# Qwiic_PT100.net
KiCad netlist of a schematic drawn in EAGLE
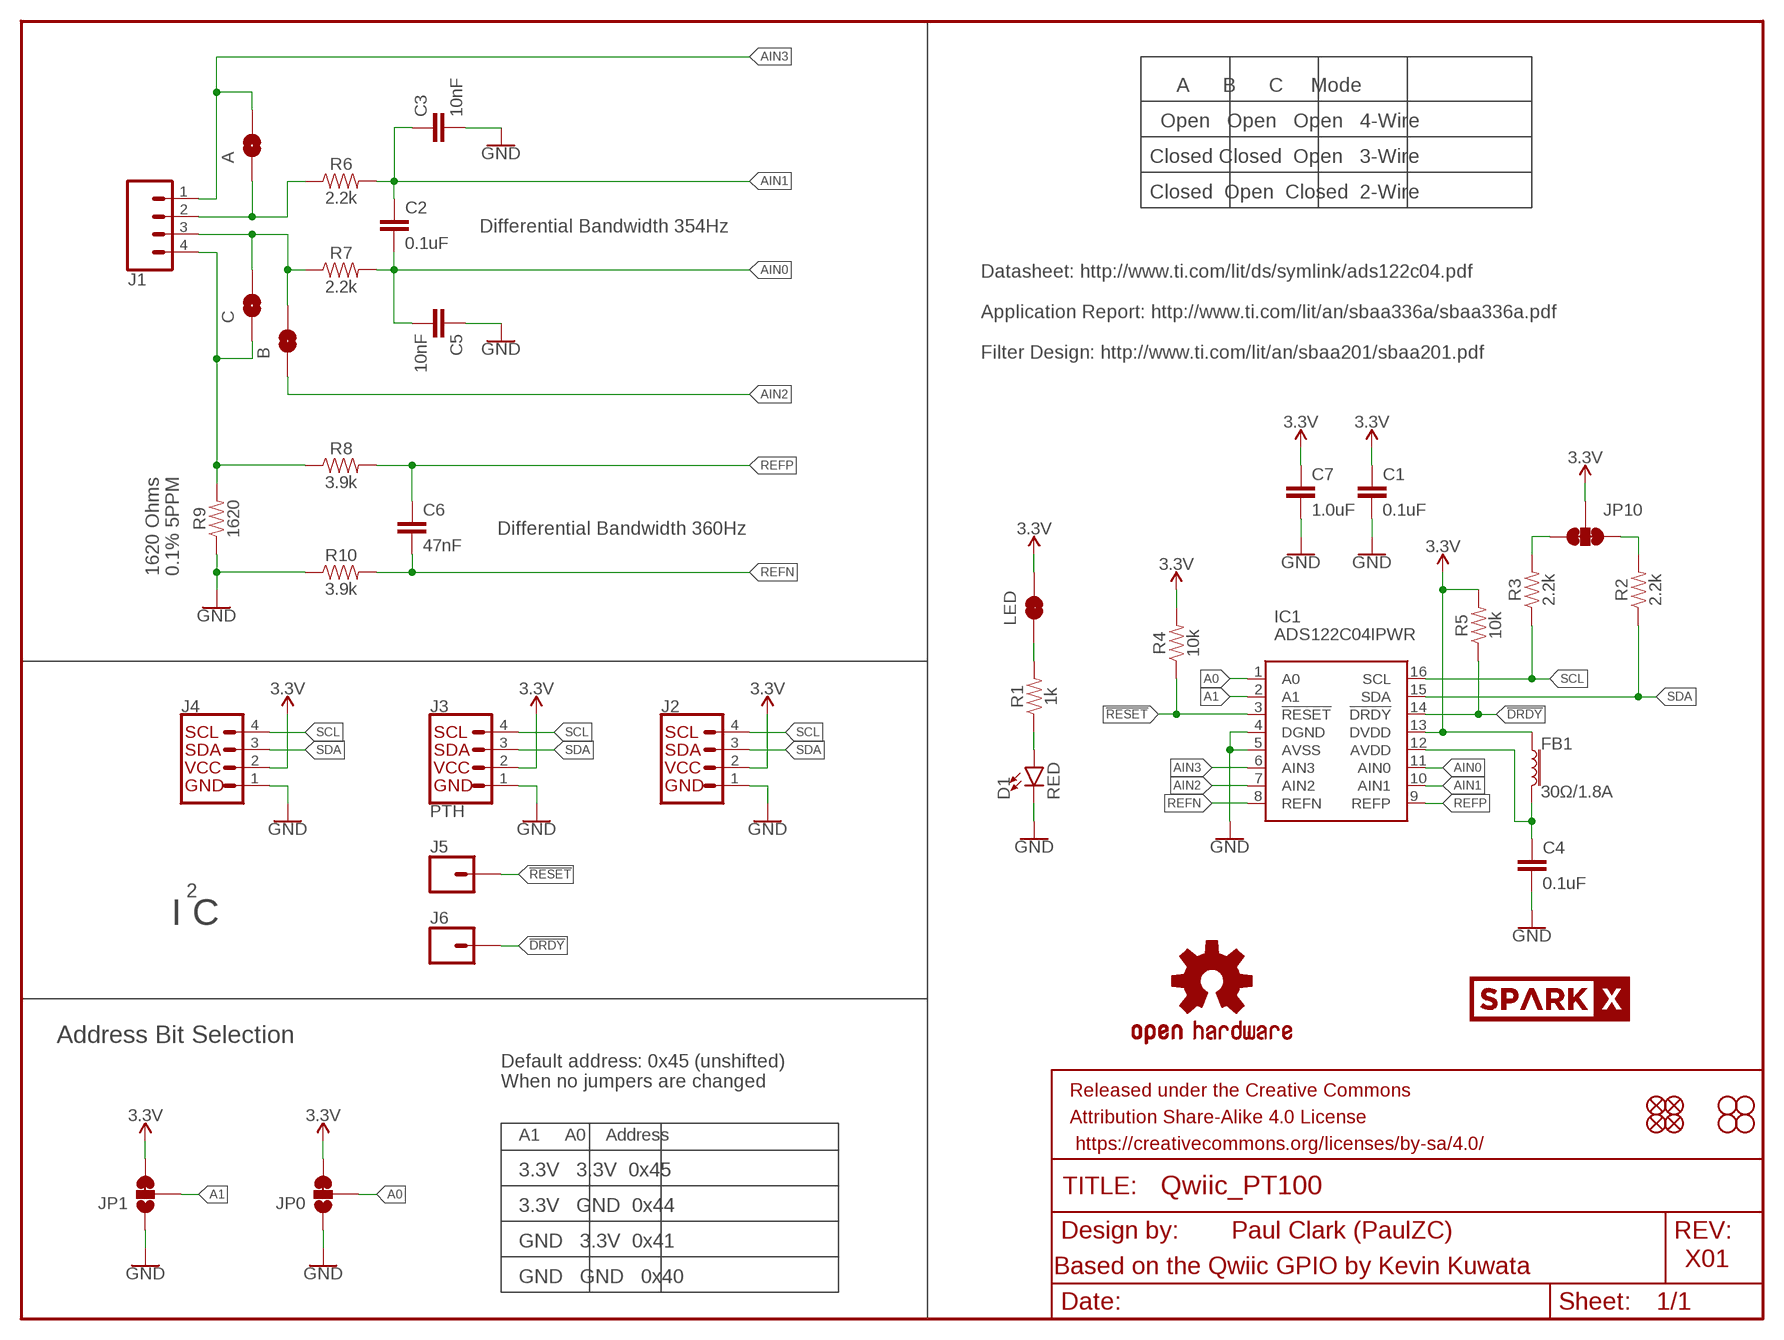
[diagram p0: schematic, sheet 1]

(export (version "E")
  (design (tool "Eeschema 10.0.6"))
  (components
    (comp (ref "A")
      (value "JUMPER-SMT_2_NO_SILK_ROUND")
      (footprint "eagle-import:SMT-JUMPER_2_NO_SILK_ROUND")
      (libsource (lib "eagle-import") (part "JUMPER-SMT_2_NO_SILK_ROUND"))
    )
    (comp (ref "B")
      (value "JUMPER-SMT_2_NO_SILK_ROUND")
      (footprint "eagle-import:SMT-JUMPER_2_NO_SILK_ROUND")
      (libsource (lib "eagle-import") (part "JUMPER-SMT_2_NO_SILK_ROUND"))
    )
    (comp (ref "C")
      (value "JUMPER-SMT_2_NO_SILK_ROUND")
      (footprint "eagle-import:SMT-JUMPER_2_NO_SILK_ROUND")
      (libsource (lib "eagle-import") (part "JUMPER-SMT_2_NO_SILK_ROUND"))
    )
    (comp (ref "C1")
      (value "0.1uF")
      (footprint "eagle-import:0603")
      (libsource (lib "eagle-import") (part "0.1UF-0603-25V-(+80/-20%)"))
    )
    (comp (ref "C2")
      (value "0.1uF")
      (footprint "eagle-import:0603")
      (libsource (lib "eagle-import") (part "0.1UF-0603-25V-5%"))
    )
    (comp (ref "C3")
      (value "10nF")
      (footprint "eagle-import:0603")
      (libsource (lib "eagle-import") (part "10NF-0603-50V-10%"))
    )
    (comp (ref "C4")
      (value "0.1uF")
      (footprint "eagle-import:0603")
      (libsource (lib "eagle-import") (part "0.1UF-0603-25V-(+80/-20%)"))
    )
    (comp (ref "C5")
      (value "10nF")
      (footprint "eagle-import:0603")
      (libsource (lib "eagle-import") (part "10NF-0603-50V-10%"))
    )
    (comp (ref "C6")
      (value "47nF")
      (footprint "eagle-import:0603")
      (libsource (lib "eagle-import") (part "47NF-0603-25V-5%"))
    )
    (comp (ref "C7")
      (value "1.0uF")
      (footprint "eagle-import:0603")
      (libsource (lib "eagle-import") (part "1.0UF-0603-16V-10%-X7R"))
    )
    (comp (ref "D1")
      (value "RED")
      (footprint "eagle-import:LED-0603")
      (libsource (lib "eagle-import") (part "LED-RED0603"))
    )
    (comp (ref "FB1")
      (value "30Ω/1.8A")
      (footprint "eagle-import:0603")
      (libsource (lib "eagle-import") (part "FERRITE_BEAD-0603"))
    )
    (comp (ref "FD1")
      (value "FIDUCIAL1X2")
      (footprint "eagle-import:FIDUCIAL-1X2")
      (libsource (lib "eagle-import") (part "FIDUCIAL1X2"))
    )
    (comp (ref "FD2")
      (value "FIDUCIAL1X2")
      (footprint "eagle-import:FIDUCIAL-1X2")
      (libsource (lib "eagle-import") (part "FIDUCIAL1X2"))
    )
    (comp (ref "FRAME1")
      (value "FRAME-LETTER")
      (footprint "eagle-import:CREATIVE_COMMONS")
      (libsource (lib "eagle-import") (part "FRAME-LETTER"))
    )
    (comp (ref "H1")
      (value "STAND-OFF")
      (footprint "eagle-import:STAND-OFF")
      (libsource (lib "eagle-import") (part "STAND-OFF"))
    )
    (comp (ref "H2")
      (value "STAND-OFF")
      (footprint "eagle-import:STAND-OFF")
      (libsource (lib "eagle-import") (part "STAND-OFF"))
    )
    (comp (ref "IC1")
      (value "ADS122C04IPWR")
      (footprint "eagle-import:SOP65P640X120-16N")
      (fields (field (name "MOUSER_PART_NUMBER") "595-ADS122C04IPWR"))
      (libsource (lib "eagle-import") (part "ADS122C04IPWR"))
    )
    (comp (ref "J1")
      (value "CONN_04LATCH")
      (footprint "eagle-import:LATCHTERMINAL-5MM-4")
      (fields (field (name "PROD_ID") "CON-14722"))
      (libsource (lib "eagle-import") (part "CONN_04LATCH"))
    )
    (comp (ref "J2")
      (value "QWIIC_RIGHT_ANGLE")
      (footprint "eagle-import:JST04_1MM_RA")
      (fields (field (name "PROD_ID") "CONN-13694"))
      (libsource (lib "eagle-import") (part "QWIIC_CONNECTORJS-1MM"))
    )
    (comp (ref "J3")
      (value "PTH")
      (footprint "eagle-import:1X04_NO_SILK")
      (libsource (lib "eagle-import") (part "I2C_STANDARD_NO_SILK"))
    )
    (comp (ref "J4")
      (value "QWIIC_RIGHT_ANGLE")
      (footprint "eagle-import:JST04_1MM_RA")
      (fields (field (name "PROD_ID") "CONN-13694"))
      (libsource (lib "eagle-import") (part "QWIIC_CONNECTORJS-1MM"))
    )
    (comp (ref "J5")
      (value "CONN_01PTH_NO_SILK_YES_STOP")
      (footprint "eagle-import:1X01_NO_SILK")
      (libsource (lib "eagle-import") (part "CONN_01PTH_NO_SILK_YES_STOP"))
    )
    (comp (ref "J6")
      (value "CONN_01PTH_NO_SILK_YES_STOP")
      (footprint "eagle-import:1X01_NO_SILK")
      (libsource (lib "eagle-import") (part "CONN_01PTH_NO_SILK_YES_STOP"))
    )
    (comp (ref "JP0")
      (value "JUMPER-SMT_3_1-NC_TRACE_SILK")
      (footprint "eagle-import:SMT-JUMPER_3_1-NC_TRACE_SILK")
      (libsource (lib "eagle-import") (part "JUMPER-SMT_3_1-NC_TRACE_SILK"))
    )
    (comp (ref "JP1")
      (value "JUMPER-SMT_3_1-NC_TRACE_SILK")
      (footprint "eagle-import:SMT-JUMPER_3_1-NC_TRACE_SILK")
      (libsource (lib "eagle-import") (part "JUMPER-SMT_3_1-NC_TRACE_SILK"))
    )
    (comp (ref "JP2")
      (value "FIDUCIAL1X2")
      (footprint "eagle-import:FIDUCIAL-1X2")
      (libsource (lib "eagle-import") (part "FIDUCIAL1X2"))
    )
    (comp (ref "JP3")
      (value "STAND-OFF")
      (footprint "eagle-import:STAND-OFF")
      (libsource (lib "eagle-import") (part "STAND-OFF"))
    )
    (comp (ref "JP4")
      (value "STAND-OFF")
      (footprint "eagle-import:STAND-OFF")
      (libsource (lib "eagle-import") (part "STAND-OFF"))
    )
    (comp (ref "JP6")
      (value "FIDUCIAL1X2")
      (footprint "eagle-import:FIDUCIAL-1X2")
      (libsource (lib "eagle-import") (part "FIDUCIAL1X2"))
    )
    (comp (ref "JP10")
      (value "JUMPER-SMT_3_2-NC_TRACE_SILK")
      (footprint "eagle-import:SMT-JUMPER_3_2-NC_TRACE_SILK")
      (libsource (lib "eagle-import") (part "JUMPER-SMT_3_2-NC_TRACE_SILK"))
    )
    (comp (ref "LED")
      (value "JUMPER-SMT_2_NC_TRACE_SILK")
      (footprint "eagle-import:SMT-JUMPER_2_NC_TRACE_SILK")
      (libsource (lib "eagle-import") (part "JUMPER-SMT_2_NC_TRACE_SILK"))
    )
    (comp (ref "LOGO1")
      (value "OSHW-LOGOMINI")
      (footprint "eagle-import:OSHW-LOGO-MINI")
      (libsource (lib "eagle-import") (part "OSHW-LOGOMINI"))
    )
    (comp (ref "R1")
      (value "1k")
      (footprint "eagle-import:0603")
      (libsource (lib "eagle-import") (part "1KOHM-0603-1/10W-1%"))
    )
    (comp (ref "R2")
      (value "2.2k")
      (footprint "eagle-import:0603")
      (libsource (lib "eagle-import") (part "2.2KOHM-0603-1/10W-1%"))
    )
    (comp (ref "R3")
      (value "2.2k")
      (footprint "eagle-import:0603")
      (libsource (lib "eagle-import") (part "2.2KOHM-0603-1/10W-1%"))
    )
    (comp (ref "R4")
      (value "10k")
      (footprint "eagle-import:0603")
      (libsource (lib "eagle-import") (part "10KOHM-0603-1/10W-1%"))
    )
    (comp (ref "R5")
      (value "10k")
      (footprint "eagle-import:0603")
      (libsource (lib "eagle-import") (part "10KOHM-0603-1/10W-1%"))
    )
    (comp (ref "R6")
      (value "2.2k")
      (footprint "eagle-import:0603")
      (libsource (lib "eagle-import") (part "2.2KOHM-0603-1/10W-1%"))
    )
    (comp (ref "R7")
      (value "2.2k")
      (footprint "eagle-import:0603")
      (libsource (lib "eagle-import") (part "2.2KOHM-0603-1/10W-1%"))
    )
    (comp (ref "R8")
      (value "3.9k")
      (footprint "eagle-import:0603")
      (libsource (lib "eagle-import") (part "3.9KOHM-0603-1/10W-1%"))
    )
    (comp (ref "R9")
      (value "1620")
      (footprint "eagle-import:0603")
      (fields (field (name "MOUSER_PART") "660-RN731JTTD1621B05") (field (name "TOLERANCE") "0.1%"))
      (libsource (lib "eagle-import") (part "RESISTOR0603"))
    )
    (comp (ref "R10")
      (value "3.9k")
      (footprint "eagle-import:0603")
      (libsource (lib "eagle-import") (part "3.9KOHM-0603-1/10W-1%"))
    )
    (comp (ref "U$1")
      (value "SPARKX-LOGO3")
      (footprint "eagle-import:SPARKX-SMALL")
      (libsource (lib "eagle-import") (part "SPARKX-LOGO3"))
    )
    (comp (ref "U$2")
      (value "SPARKX-LOGO3")
      (footprint "eagle-import:SPARKX-SMALL")
      (libsource (lib "eagle-import") (part "SPARKX-LOGO3"))
    )
  )
  (nets
    (net (code "1") (name "/~{DRDY}") (class "Default")
      (node (ref "IC1") (pin "14") (pinfunction "~{DRDY}_14") (pintype "output"))
      (node (ref "J6") (pin "1") (pinfunction "1_1") (pintype "passive"))
      (node (ref "R5") (pin "1") (pinfunction "1_1") (pintype "passive"))
    )
    (net (code "2") (name "/~{RESET}") (class "Default")
      (node (ref "IC1") (pin "3") (pinfunction "~{RESET}_3") (pintype "input"))
      (node (ref "J5") (pin "1") (pinfunction "1_1") (pintype "passive"))
      (node (ref "R4") (pin "1") (pinfunction "1_1") (pintype "passive"))
    )
    (net (code "3") (name "3.3V") (class "Default")
      (node (ref "C1") (pin "1") (pinfunction "1_1") (pintype "passive"))
      (node (ref "C7") (pin "1") (pinfunction "1_1") (pintype "passive"))
      (node (ref "FB1") (pin "1") (pinfunction "1_1") (pintype "passive"))
      (node (ref "IC1") (pin "13") (pinfunction "DVDD_13") (pintype "power_in"))
      (node (ref "J2") (pin "2") (pinfunction "2_2") (pintype "power_in"))
      (node (ref "J3") (pin "2") (pinfunction "2_2") (pintype "power_in"))
      (node (ref "J4") (pin "2") (pinfunction "2_2") (pintype "power_in"))
      (node (ref "JP0") (pin "3") (pinfunction "3_3") (pintype "passive"))
      (node (ref "JP1") (pin "3") (pinfunction "3_3") (pintype "passive"))
      (node (ref "JP10") (pin "2") (pinfunction "2_2") (pintype "passive"))
      (node (ref "LED") (pin "2") (pinfunction "2_2") (pintype "passive"))
      (node (ref "R4") (pin "2") (pinfunction "2_2") (pintype "passive"))
      (node (ref "R5") (pin "2") (pinfunction "2_2") (pintype "passive"))
    )
    (net (code "4") (name "A0") (class "Default")
      (node (ref "IC1") (pin "1") (pinfunction "A0_1") (pintype "input"))
      (node (ref "JP0") (pin "2") (pinfunction "2_2") (pintype "passive"))
    )
    (net (code "5") (name "A1") (class "Default")
      (node (ref "IC1") (pin "2") (pinfunction "A1_2") (pintype "input"))
      (node (ref "JP1") (pin "2") (pinfunction "2_2") (pintype "passive"))
    )
    (net (code "6") (name "AIN0") (class "Default")
      (node (ref "C2") (pin "2") (pinfunction "2_2") (pintype "passive"))
      (node (ref "C5") (pin "2") (pinfunction "2_2") (pintype "passive"))
      (node (ref "IC1") (pin "11") (pinfunction "AIN0_11") (pintype "input"))
      (node (ref "R7") (pin "2") (pinfunction "2_2") (pintype "passive"))
    )
    (net (code "7") (name "AIN1") (class "Default")
      (node (ref "C2") (pin "1") (pinfunction "1_1") (pintype "passive"))
      (node (ref "C3") (pin "1") (pinfunction "1_1") (pintype "passive"))
      (node (ref "IC1") (pin "10") (pinfunction "AIN1_10") (pintype "input"))
      (node (ref "R6") (pin "2") (pinfunction "2_2") (pintype "passive"))
    )
    (net (code "8") (name "AIN2") (class "Default")
      (node (ref "B") (pin "1") (pinfunction "1_1") (pintype "passive"))
      (node (ref "IC1") (pin "7") (pinfunction "AIN2_7") (pintype "input"))
    )
    (net (code "9") (name "AIN3") (class "Default")
      (node (ref "A") (pin "2") (pinfunction "2_2") (pintype "passive"))
      (node (ref "IC1") (pin "6") (pinfunction "AIN3_6") (pintype "input"))
      (node (ref "J1") (pin "1") (pinfunction "1_1") (pintype "passive"))
    )
    (net (code "10") (name "GND") (class "Default")
      (node (ref "C1") (pin "2") (pinfunction "2_2") (pintype "passive"))
      (node (ref "C3") (pin "2") (pinfunction "2_2") (pintype "passive"))
      (node (ref "C4") (pin "2") (pinfunction "2_2") (pintype "passive"))
      (node (ref "C5") (pin "1") (pinfunction "1_1") (pintype "passive"))
      (node (ref "C7") (pin "2") (pinfunction "2_2") (pintype "passive"))
      (node (ref "D1") (pin "C") (pinfunction "C_C") (pintype "passive"))
      (node (ref "IC1") (pin "4") (pinfunction "DGND_4") (pintype "power_in"))
      (node (ref "IC1") (pin "5") (pinfunction "AVSS_5") (pintype "power_in"))
      (node (ref "J2") (pin "1") (pinfunction "1_1") (pintype "power_in"))
      (node (ref "J3") (pin "1") (pinfunction "1_1") (pintype "power_in"))
      (node (ref "J4") (pin "1") (pinfunction "1_1") (pintype "power_in"))
      (node (ref "JP0") (pin "1") (pinfunction "1_1") (pintype "passive"))
      (node (ref "JP1") (pin "1") (pinfunction "1_1") (pintype "passive"))
      (node (ref "R10") (pin "1") (pinfunction "1_1") (pintype "passive"))
      (node (ref "R9") (pin "1") (pinfunction "1_1") (pintype "passive"))
    )
    (net (code "11") (name "Net-(A-Pad1)") (class "Default")
      (node (ref "A") (pin "1") (pinfunction "1_1") (pintype "passive"))
      (node (ref "J1") (pin "2") (pinfunction "2_2") (pintype "passive"))
      (node (ref "R6") (pin "1") (pinfunction "1_1") (pintype "passive"))
    )
    (net (code "12") (name "Net-(B-Pad2)") (class "Default")
      (node (ref "B") (pin "2") (pinfunction "2_2") (pintype "passive"))
      (node (ref "C") (pin "2") (pinfunction "2_2") (pintype "passive"))
      (node (ref "J1") (pin "3") (pinfunction "3_3") (pintype "passive"))
      (node (ref "R7") (pin "1") (pinfunction "1_1") (pintype "passive"))
    )
    (net (code "13") (name "Net-(C-Pad1)") (class "Default")
      (node (ref "C") (pin "1") (pinfunction "1_1") (pintype "passive"))
      (node (ref "J1") (pin "4") (pinfunction "4_4") (pintype "passive"))
      (node (ref "R8") (pin "1") (pinfunction "1_1") (pintype "passive"))
      (node (ref "R9") (pin "2") (pinfunction "2_2") (pintype "passive"))
    )
    (net (code "14") (name "Net-(D1-PadA)") (class "Default")
      (node (ref "D1") (pin "A") (pinfunction "A_A") (pintype "passive"))
      (node (ref "R1") (pin "1") (pinfunction "1_1") (pintype "passive"))
    )
    (net (code "15") (name "Net-(IC1-AVDD)") (class "Default")
      (node (ref "C4") (pin "1") (pinfunction "1_1") (pintype "passive"))
      (node (ref "FB1") (pin "2") (pinfunction "2_2") (pintype "passive"))
      (node (ref "IC1") (pin "12") (pinfunction "AVDD_12") (pintype "power_in"))
    )
    (net (code "16") (name "Net-(JP10-Pad1)") (class "Default")
      (node (ref "JP10") (pin "1") (pinfunction "1_1") (pintype "passive"))
      (node (ref "R2") (pin "2") (pinfunction "2_2") (pintype "passive"))
    )
    (net (code "17") (name "Net-(JP10-Pad3)") (class "Default")
      (node (ref "JP10") (pin "3") (pinfunction "3_3") (pintype "passive"))
      (node (ref "R3") (pin "2") (pinfunction "2_2") (pintype "passive"))
    )
    (net (code "18") (name "Net-(LED-Pad1)") (class "Default")
      (node (ref "LED") (pin "1") (pinfunction "1_1") (pintype "passive"))
      (node (ref "R1") (pin "2") (pinfunction "2_2") (pintype "passive"))
    )
    (net (code "19") (name "REFN") (class "Default")
      (node (ref "C6") (pin "2") (pinfunction "2_2") (pintype "passive"))
      (node (ref "IC1") (pin "8") (pinfunction "REFN_8") (pintype "input"))
      (node (ref "R10") (pin "2") (pinfunction "2_2") (pintype "passive"))
    )
    (net (code "20") (name "REFP") (class "Default")
      (node (ref "C6") (pin "1") (pinfunction "1_1") (pintype "passive"))
      (node (ref "IC1") (pin "9") (pinfunction "REFP_9") (pintype "input"))
      (node (ref "R8") (pin "2") (pinfunction "2_2") (pintype "passive"))
    )
    (net (code "21") (name "SCL") (class "Default")
      (node (ref "IC1") (pin "16") (pinfunction "SCL_16") (pintype "bidirectional"))
      (node (ref "J2") (pin "4") (pinfunction "4_4") (pintype "passive"))
      (node (ref "J3") (pin "4") (pinfunction "4_4") (pintype "passive"))
      (node (ref "J4") (pin "4") (pinfunction "4_4") (pintype "passive"))
      (node (ref "R3") (pin "1") (pinfunction "1_1") (pintype "passive"))
    )
    (net (code "22") (name "SDA") (class "Default")
      (node (ref "IC1") (pin "15") (pinfunction "SDA_15") (pintype "bidirectional"))
      (node (ref "J2") (pin "3") (pinfunction "3_3") (pintype "passive"))
      (node (ref "J3") (pin "3") (pinfunction "3_3") (pintype "passive"))
      (node (ref "J4") (pin "3") (pinfunction "3_3") (pintype "passive"))
      (node (ref "R2") (pin "1") (pinfunction "1_1") (pintype "passive"))
    )
  )
)
